# ASD2302.net
KiCad netlist of a schematic drawn in EAGLE
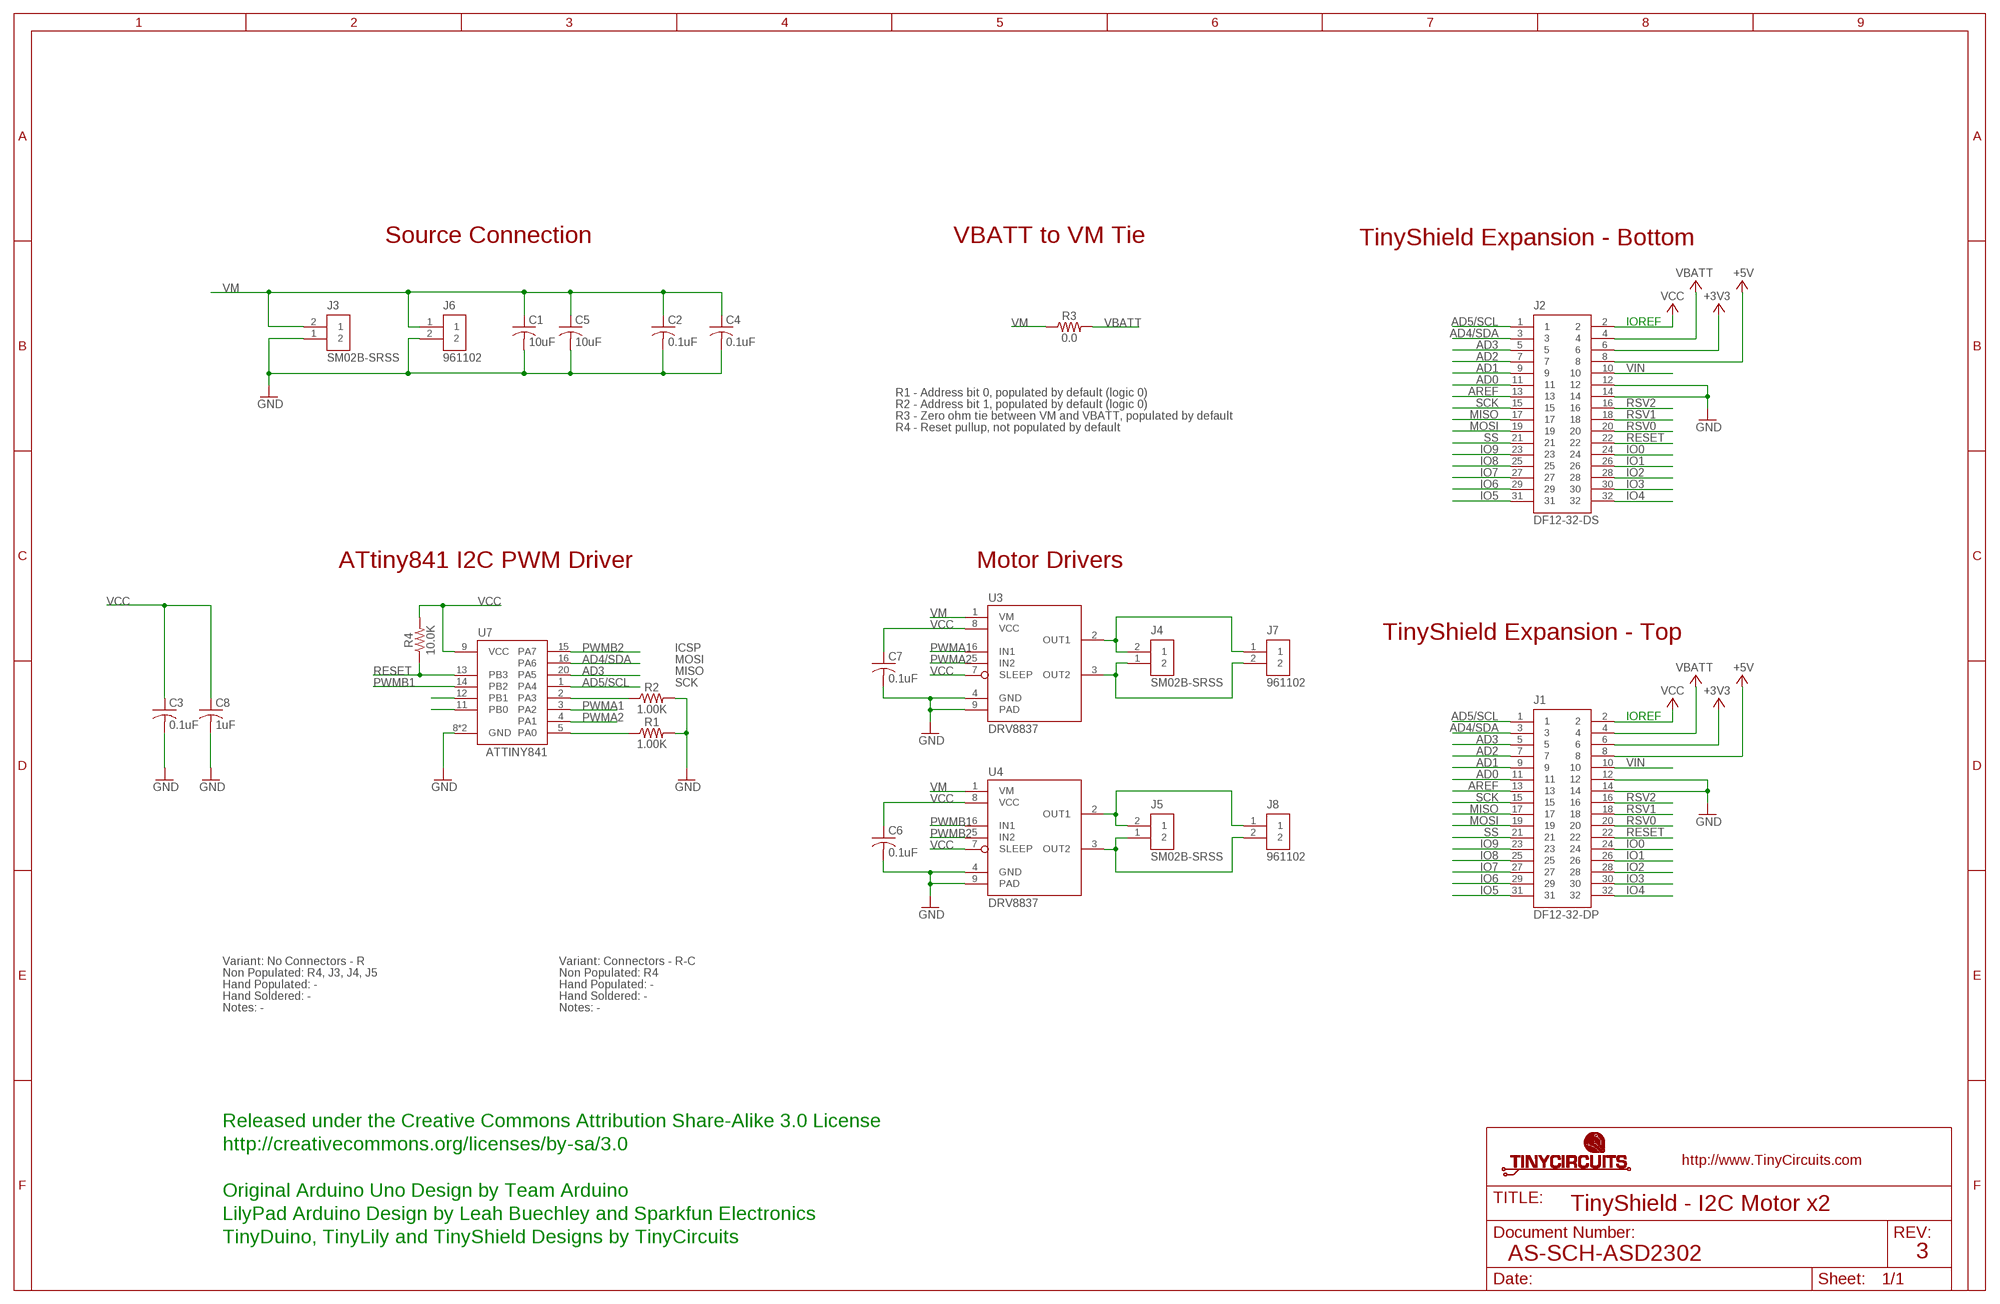
[diagram p0: schematic, sheet 1]

(export (version "E")
  (design (tool "Eeschema 10.0.6"))
  (components
    (comp (ref "C1")
      (value "10uF")
      (footprint "eagle-import:C0805")
      (fields (field (name "PARTNO") "AS-ITM-00045"))
      (libsource (lib "eagle-import") (part "AS-ITM-00045"))
    )
    (comp (ref "C2")
      (value "0.1uF")
      (footprint "eagle-import:C0402")
      (fields (field (name "PARTNO") "AS-ITM-00008"))
      (libsource (lib "eagle-import") (part "AS-ITM-00008"))
    )
    (comp (ref "C3")
      (value "0.1uF")
      (footprint "eagle-import:C0402")
      (fields (field (name "PARTNO") "AS-ITM-00008") (field (name "PARTNO_1") "AS-ITM-00008"))
      (libsource (lib "eagle-import") (part "AS-ITM-00008"))
    )
    (comp (ref "C4")
      (value "0.1uF")
      (footprint "eagle-import:C0402")
      (fields (field (name "PARTNO") "AS-ITM-00008") (field (name "PARTNO_1") "AS-ITM-00008"))
      (libsource (lib "eagle-import") (part "AS-ITM-00008"))
    )
    (comp (ref "C5")
      (value "10uF")
      (footprint "eagle-import:C0805")
      (fields (field (name "PARTNO") "AS-ITM-00045"))
      (libsource (lib "eagle-import") (part "AS-ITM-00045"))
    )
    (comp (ref "C6")
      (value "0.1uF")
      (footprint "eagle-import:C0402")
      (fields (field (name "PARTNO") "AS-ITM-00008") (field (name "PARTNO_1") "AS-ITM-00008"))
      (libsource (lib "eagle-import") (part "AS-ITM-00008"))
    )
    (comp (ref "C7")
      (value "0.1uF")
      (footprint "eagle-import:C0402")
      (fields (field (name "PARTNO") "AS-ITM-00008") (field (name "PARTNO_1") "AS-ITM-00008"))
      (libsource (lib "eagle-import") (part "AS-ITM-00008"))
    )
    (comp (ref "C8")
      (value "1uF")
      (footprint "eagle-import:C0402")
      (fields (field (name "PARTNO") "AS-ITM-00105") (field (name "PARTNO_1") "AS-ITM-00105"))
      (libsource (lib "eagle-import") (part "AS-ITM-00105"))
    )
    (comp (ref "J1")
      (value "DF12-32-DP")
      (footprint "eagle-import:DF12-32-DP")
      (fields (field (name "PARTNO") "AS-ITM-00015") (field (name "PARTNO_1") "AS-ITM-00015"))
      (libsource (lib "eagle-import") (part "AS-ITM-00015"))
    )
    (comp (ref "J2")
      (value "DF12-32-DS")
      (footprint "eagle-import:DF12-32-DS")
      (fields (field (name "PARTNO") "AS-ITM-00012") (field (name "PARTNO_1") "AS-ITM-00012"))
      (libsource (lib "eagle-import") (part "AS-ITM-00012"))
    )
    (comp (ref "J3")
      (value "SM02B-SRSS")
      (footprint "eagle-import:JST_SH_2X1")
      (fields (field (name "PARTNO") "AS-ITM-00231"))
      (libsource (lib "eagle-import") (part "AS-ITM-00231"))
    )
    (comp (ref "J4")
      (value "SM02B-SRSS")
      (footprint "eagle-import:JST_SH_2X1")
      (fields (field (name "PARTNO") "AS-ITM-00231"))
      (libsource (lib "eagle-import") (part "AS-ITM-00231"))
    )
    (comp (ref "J5")
      (value "SM02B-SRSS")
      (footprint "eagle-import:JST_SH_2X1")
      (fields (field (name "PARTNO") "AS-ITM-00231"))
      (libsource (lib "eagle-import") (part "AS-ITM-00231"))
    )
    (comp (ref "J6")
      (value "961102")
      (footprint "eagle-import:2X.1_")
      (fields (field (name "PARTNO") "AS-ITM-00044"))
      (libsource (lib "eagle-import") (part "AS-ITM-00044"))
    )
    (comp (ref "J7")
      (value "961102")
      (footprint "eagle-import:2X.1_")
      (fields (field (name "PARTNO") "AS-ITM-00044"))
      (libsource (lib "eagle-import") (part "AS-ITM-00044"))
    )
    (comp (ref "J8")
      (value "961102")
      (footprint "eagle-import:2X.1_")
      (fields (field (name "PARTNO") "AS-ITM-00044"))
      (libsource (lib "eagle-import") (part "AS-ITM-00044"))
    )
    (comp (ref "R1")
      (value "1.00K")
      (footprint "eagle-import:0402")
      (fields (field (name "PARTNO") "AS-ITM-00003") (field (name "PARTNO_1") "AS-ITM-00003"))
      (libsource (lib "eagle-import") (part "AS-ITM-00003"))
    )
    (comp (ref "R2")
      (value "1.00K")
      (footprint "eagle-import:0402")
      (fields (field (name "PARTNO") "AS-ITM-00003") (field (name "PARTNO_1") "AS-ITM-00003"))
      (libsource (lib "eagle-import") (part "AS-ITM-00003"))
    )
    (comp (ref "R3")
      (value "0.0")
      (footprint "eagle-import:0402")
      (fields (field (name "PARTNO") "AS-ITM-00076"))
      (libsource (lib "eagle-import") (part "AS-ITM-00076"))
    )
    (comp (ref "R4")
      (value "10.0K")
      (footprint "eagle-import:0402")
      (fields (field (name "PARTNO") "AS-ITM-00032"))
      (libsource (lib "eagle-import") (part "AS-ITM-00032"))
    )
    (comp (ref "U3")
      (value "DRV8837")
      (footprint "eagle-import:WSON-8")
      (fields (field (name "PARTNO") "AS-ITM-00042"))
      (libsource (lib "eagle-import") (part "AS-ITM-00042"))
    )
    (comp (ref "U4")
      (value "DRV8837")
      (footprint "eagle-import:WSON-8")
      (fields (field (name "PARTNO") "AS-ITM-00042"))
      (libsource (lib "eagle-import") (part "AS-ITM-00042"))
    )
    (comp (ref "U7")
      (value "ATTINY841")
      (footprint "eagle-import:VQFN-20")
      (fields (field (name "PARTNO") "AS-ITM-00255"))
      (libsource (lib "eagle-import") (part "AS-ITM-00255"))
    )
  )
  (nets
    (net (code "1") (name "+3V3") (class "Default")
      (node (ref "J1") (pin "6") (pinfunction "6_6") (pintype "bidirectional"))
      (node (ref "J2") (pin "6") (pinfunction "6_6") (pintype "bidirectional"))
    )
    (net (code "2") (name "+5V") (class "Default")
      (node (ref "J1") (pin "8") (pinfunction "8_8") (pintype "bidirectional"))
      (node (ref "J2") (pin "8") (pinfunction "8_8") (pintype "bidirectional"))
    )
    (net (code "3") (name "/AD0") (class "Default")
      (node (ref "J1") (pin "11") (pinfunction "11_11") (pintype "bidirectional"))
      (node (ref "J2") (pin "11") (pinfunction "11_11") (pintype "bidirectional"))
    )
    (net (code "4") (name "/AD1") (class "Default")
      (node (ref "J1") (pin "9") (pinfunction "9_9") (pintype "bidirectional"))
      (node (ref "J2") (pin "9") (pinfunction "9_9") (pintype "bidirectional"))
    )
    (net (code "5") (name "/AD2") (class "Default")
      (node (ref "J1") (pin "7") (pinfunction "7_7") (pintype "bidirectional"))
      (node (ref "J2") (pin "7") (pinfunction "7_7") (pintype "bidirectional"))
    )
    (net (code "6") (name "/AD3") (class "Default")
      (node (ref "J1") (pin "5") (pinfunction "5_5") (pintype "bidirectional"))
      (node (ref "J2") (pin "5") (pinfunction "5_5") (pintype "bidirectional"))
      (node (ref "U7") (pin "20") (pinfunction "PA5_20") (pintype "bidirectional"))
    )
    (net (code "7") (name "/AD4{slash}SDA") (class "Default")
      (node (ref "J1") (pin "3") (pinfunction "3_3") (pintype "bidirectional"))
      (node (ref "J2") (pin "3") (pinfunction "3_3") (pintype "bidirectional"))
      (node (ref "U7") (pin "16") (pinfunction "PA6_16") (pintype "bidirectional"))
    )
    (net (code "8") (name "/AD5{slash}SCL") (class "Default")
      (node (ref "J1") (pin "1") (pinfunction "1_1") (pintype "bidirectional"))
      (node (ref "J2") (pin "1") (pinfunction "1_1") (pintype "bidirectional"))
      (node (ref "U7") (pin "1") (pinfunction "PA4_1") (pintype "bidirectional"))
    )
    (net (code "9") (name "/AREF") (class "Default")
      (node (ref "J1") (pin "13") (pinfunction "13_13") (pintype "bidirectional"))
      (node (ref "J2") (pin "13") (pinfunction "13_13") (pintype "bidirectional"))
    )
    (net (code "10") (name "/IO0") (class "Default")
      (node (ref "J1") (pin "24") (pinfunction "24_24") (pintype "bidirectional"))
      (node (ref "J2") (pin "24") (pinfunction "24_24") (pintype "bidirectional"))
    )
    (net (code "11") (name "/IO1") (class "Default")
      (node (ref "J1") (pin "26") (pinfunction "26_26") (pintype "bidirectional"))
      (node (ref "J2") (pin "26") (pinfunction "26_26") (pintype "bidirectional"))
    )
    (net (code "12") (name "/IO2") (class "Default")
      (node (ref "J1") (pin "28") (pinfunction "28_28") (pintype "bidirectional"))
      (node (ref "J2") (pin "28") (pinfunction "28_28") (pintype "bidirectional"))
    )
    (net (code "13") (name "/IO3") (class "Default")
      (node (ref "J1") (pin "30") (pinfunction "30_30") (pintype "bidirectional"))
      (node (ref "J2") (pin "30") (pinfunction "30_30") (pintype "bidirectional"))
    )
    (net (code "14") (name "/IO4") (class "Default")
      (node (ref "J1") (pin "32") (pinfunction "32_32") (pintype "bidirectional"))
      (node (ref "J2") (pin "32") (pinfunction "32_32") (pintype "bidirectional"))
    )
    (net (code "15") (name "/IO5") (class "Default")
      (node (ref "J1") (pin "31") (pinfunction "31_31") (pintype "bidirectional"))
      (node (ref "J2") (pin "31") (pinfunction "31_31") (pintype "bidirectional"))
    )
    (net (code "16") (name "/IO6") (class "Default")
      (node (ref "J1") (pin "29") (pinfunction "29_29") (pintype "bidirectional"))
      (node (ref "J2") (pin "29") (pinfunction "29_29") (pintype "bidirectional"))
    )
    (net (code "17") (name "/IO7") (class "Default")
      (node (ref "J1") (pin "27") (pinfunction "27_27") (pintype "bidirectional"))
      (node (ref "J2") (pin "27") (pinfunction "27_27") (pintype "bidirectional"))
    )
    (net (code "18") (name "/IO8") (class "Default")
      (node (ref "J1") (pin "25") (pinfunction "25_25") (pintype "bidirectional"))
      (node (ref "J2") (pin "25") (pinfunction "25_25") (pintype "bidirectional"))
    )
    (net (code "19") (name "/IO9") (class "Default")
      (node (ref "J1") (pin "23") (pinfunction "23_23") (pintype "bidirectional"))
      (node (ref "J2") (pin "23") (pinfunction "23_23") (pintype "bidirectional"))
    )
    (net (code "20") (name "/MISO") (class "Default")
      (node (ref "J1") (pin "17") (pinfunction "17_17") (pintype "bidirectional"))
      (node (ref "J2") (pin "17") (pinfunction "17_17") (pintype "bidirectional"))
    )
    (net (code "21") (name "/MOSI") (class "Default")
      (node (ref "J1") (pin "19") (pinfunction "19_19") (pintype "bidirectional"))
      (node (ref "J2") (pin "19") (pinfunction "19_19") (pintype "bidirectional"))
    )
    (net (code "22") (name "/PWMA1") (class "Default")
      (node (ref "U3") (pin "6") (pinfunction "IN1_6") (pintype "power_in"))
      (node (ref "U7") (pin "3") (pinfunction "PA2_3") (pintype "bidirectional"))
    )
    (net (code "23") (name "/PWMA2") (class "Default")
      (node (ref "U3") (pin "5") (pinfunction "IN2_5") (pintype "power_in"))
      (node (ref "U7") (pin "4") (pinfunction "PA1_4") (pintype "bidirectional"))
    )
    (net (code "24") (name "/PWMB1") (class "Default")
      (node (ref "U4") (pin "6") (pinfunction "IN1_6") (pintype "power_in"))
      (node (ref "U7") (pin "14") (pinfunction "PB2_14") (pintype "bidirectional"))
    )
    (net (code "25") (name "/PWMB2") (class "Default")
      (node (ref "U4") (pin "5") (pinfunction "IN2_5") (pintype "power_in"))
      (node (ref "U7") (pin "15") (pinfunction "PA7_15") (pintype "bidirectional"))
    )
    (net (code "26") (name "/RESET") (class "Default")
      (node (ref "J1") (pin "22") (pinfunction "22_22") (pintype "bidirectional"))
      (node (ref "J2") (pin "22") (pinfunction "22_22") (pintype "bidirectional"))
      (node (ref "R4") (pin "1") (pinfunction "1_1") (pintype "passive"))
      (node (ref "U7") (pin "13") (pinfunction "PB3_13") (pintype "bidirectional"))
    )
    (net (code "27") (name "/RSV0") (class "Default")
      (node (ref "J1") (pin "20") (pinfunction "20_20") (pintype "bidirectional"))
      (node (ref "J2") (pin "20") (pinfunction "20_20") (pintype "bidirectional"))
    )
    (net (code "28") (name "/RSV1") (class "Default")
      (node (ref "J1") (pin "18") (pinfunction "18_18") (pintype "bidirectional"))
      (node (ref "J2") (pin "18") (pinfunction "18_18") (pintype "bidirectional"))
    )
    (net (code "29") (name "/RSV2") (class "Default")
      (node (ref "J1") (pin "16") (pinfunction "16_16") (pintype "bidirectional"))
      (node (ref "J2") (pin "16") (pinfunction "16_16") (pintype "bidirectional"))
    )
    (net (code "30") (name "/SCK") (class "Default")
      (node (ref "J1") (pin "15") (pinfunction "15_15") (pintype "bidirectional"))
      (node (ref "J2") (pin "15") (pinfunction "15_15") (pintype "bidirectional"))
    )
    (net (code "31") (name "/SS") (class "Default")
      (node (ref "J1") (pin "21") (pinfunction "21_21") (pintype "bidirectional"))
      (node (ref "J2") (pin "21") (pinfunction "21_21") (pintype "bidirectional"))
    )
    (net (code "32") (name "/VIN") (class "Default")
      (node (ref "J1") (pin "10") (pinfunction "10_10") (pintype "bidirectional"))
      (node (ref "J2") (pin "10") (pinfunction "10_10") (pintype "bidirectional"))
    )
    (net (code "33") (name "/VM") (class "Default")
      (node (ref "C1") (pin "1") (pinfunction "1_1") (pintype "passive"))
      (node (ref "C2") (pin "1") (pinfunction "1_1") (pintype "passive"))
      (node (ref "C4") (pin "1") (pinfunction "1_1") (pintype "passive"))
      (node (ref "C5") (pin "1") (pinfunction "1_1") (pintype "passive"))
      (node (ref "J3") (pin "2") (pinfunction "1_2") (pintype "bidirectional"))
      (node (ref "J6") (pin "1") (pinfunction "1_1") (pintype "bidirectional"))
      (node (ref "R3") (pin "1") (pinfunction "1_1") (pintype "passive"))
      (node (ref "U3") (pin "1") (pinfunction "VM_1") (pintype "bidirectional"))
      (node (ref "U4") (pin "1") (pinfunction "VM_1") (pintype "bidirectional"))
    )
    (net (code "34") (name "GND") (class "Default")
      (node (ref "C1") (pin "2") (pinfunction "2_2") (pintype "passive"))
      (node (ref "C2") (pin "2") (pinfunction "2_2") (pintype "passive"))
      (node (ref "C3") (pin "2") (pinfunction "2_2") (pintype "passive"))
      (node (ref "C4") (pin "2") (pinfunction "2_2") (pintype "passive"))
      (node (ref "C5") (pin "2") (pinfunction "2_2") (pintype "passive"))
      (node (ref "C6") (pin "2") (pinfunction "2_2") (pintype "passive"))
      (node (ref "C7") (pin "2") (pinfunction "2_2") (pintype "passive"))
      (node (ref "C8") (pin "2") (pinfunction "2_2") (pintype "passive"))
      (node (ref "J1") (pin "12") (pinfunction "12_12") (pintype "bidirectional"))
      (node (ref "J1") (pin "14") (pinfunction "14_14") (pintype "bidirectional"))
      (node (ref "J2") (pin "12") (pinfunction "12_12") (pintype "bidirectional"))
      (node (ref "J2") (pin "14") (pinfunction "14_14") (pintype "bidirectional"))
      (node (ref "J3") (pin "1") (pinfunction "2_1") (pintype "bidirectional"))
      (node (ref "J6") (pin "2") (pinfunction "2_2") (pintype "bidirectional"))
      (node (ref "R1") (pin "2") (pinfunction "2_2") (pintype "passive"))
      (node (ref "R2") (pin "2") (pinfunction "2_2") (pintype "passive"))
      (node (ref "U3") (pin "4") (pinfunction "GND_4") (pintype "power_in"))
      (node (ref "U3") (pin "9") (pinfunction "PAD_9") (pintype "power_in"))
      (node (ref "U4") (pin "4") (pinfunction "GND_4") (pintype "power_in"))
      (node (ref "U4") (pin "9") (pinfunction "PAD_9") (pintype "power_in"))
      (node (ref "U7") (pin "8") (pinfunction "GND_8") (pintype "bidirectional"))
      (node (ref "U7") (pin "PAD") (pinfunction "GND_PAD") (pintype "bidirectional"))
    )
    (net (code "35") (name "Net-(J4-1)") (class "Default")
      (node (ref "J4") (pin "2") (pinfunction "1_2") (pintype "bidirectional"))
      (node (ref "J7") (pin "1") (pinfunction "1_1") (pintype "bidirectional"))
      (node (ref "U3") (pin "2") (pinfunction "OUT1_2") (pintype "bidirectional"))
    )
    (net (code "36") (name "Net-(J4-2)") (class "Default")
      (node (ref "J4") (pin "1") (pinfunction "2_1") (pintype "bidirectional"))
      (node (ref "J7") (pin "2") (pinfunction "2_2") (pintype "bidirectional"))
      (node (ref "U3") (pin "3") (pinfunction "OUT2_3") (pintype "bidirectional"))
    )
    (net (code "37") (name "Net-(J5-1)") (class "Default")
      (node (ref "J5") (pin "2") (pinfunction "1_2") (pintype "bidirectional"))
      (node (ref "J8") (pin "1") (pinfunction "1_1") (pintype "bidirectional"))
      (node (ref "U4") (pin "2") (pinfunction "OUT1_2") (pintype "bidirectional"))
    )
    (net (code "38") (name "Net-(J5-2)") (class "Default")
      (node (ref "J5") (pin "1") (pinfunction "2_1") (pintype "bidirectional"))
      (node (ref "J8") (pin "2") (pinfunction "2_2") (pintype "bidirectional"))
      (node (ref "U4") (pin "3") (pinfunction "OUT2_3") (pintype "bidirectional"))
    )
    (net (code "39") (name "Net-(U7-PA0)") (class "Default")
      (node (ref "R1") (pin "1") (pinfunction "1_1") (pintype "passive"))
      (node (ref "U7") (pin "5") (pinfunction "PA0_5") (pintype "bidirectional"))
    )
    (net (code "40") (name "Net-(U7-PA3)") (class "Default")
      (node (ref "R2") (pin "1") (pinfunction "1_1") (pintype "passive"))
      (node (ref "U7") (pin "2") (pinfunction "PA3_2") (pintype "bidirectional"))
    )
    (net (code "41") (name "VBATT") (class "Default")
      (node (ref "J1") (pin "4") (pinfunction "4_4") (pintype "bidirectional"))
      (node (ref "J2") (pin "4") (pinfunction "4_4") (pintype "bidirectional"))
      (node (ref "R3") (pin "2") (pinfunction "2_2") (pintype "passive"))
    )
    (net (code "42") (name "VCC") (class "Default")
      (node (ref "C3") (pin "1") (pinfunction "1_1") (pintype "passive"))
      (node (ref "C6") (pin "1") (pinfunction "1_1") (pintype "passive"))
      (node (ref "C7") (pin "1") (pinfunction "1_1") (pintype "passive"))
      (node (ref "C8") (pin "1") (pinfunction "1_1") (pintype "passive"))
      (node (ref "J1") (pin "2") (pinfunction "2_2") (pintype "bidirectional"))
      (node (ref "J2") (pin "2") (pinfunction "2_2") (pintype "bidirectional"))
      (node (ref "R4") (pin "2") (pinfunction "2_2") (pintype "passive"))
      (node (ref "U3") (pin "7") (pinfunction "SLEEP_7") (pintype "bidirectional"))
      (node (ref "U3") (pin "8") (pinfunction "VCC_8") (pintype "bidirectional"))
      (node (ref "U4") (pin "7") (pinfunction "SLEEP_7") (pintype "bidirectional"))
      (node (ref "U4") (pin "8") (pinfunction "VCC_8") (pintype "bidirectional"))
      (node (ref "U7") (pin "9") (pinfunction "VCC_9") (pintype "bidirectional"))
    )
    (net (code "43") (name "unconnected-(U7-PB0-Pad11)") (class "Default")
      (node (ref "U7") (pin "11") (pinfunction "PB0_11") (pintype "bidirectional"))
    )
    (net (code "44") (name "unconnected-(U7-PB1-Pad12)") (class "Default")
      (node (ref "U7") (pin "12") (pinfunction "PB1_12") (pintype "bidirectional"))
    )
  )
)
